# FPC-024.net
KiCad netlist of a schematic drawn in EasyEDA
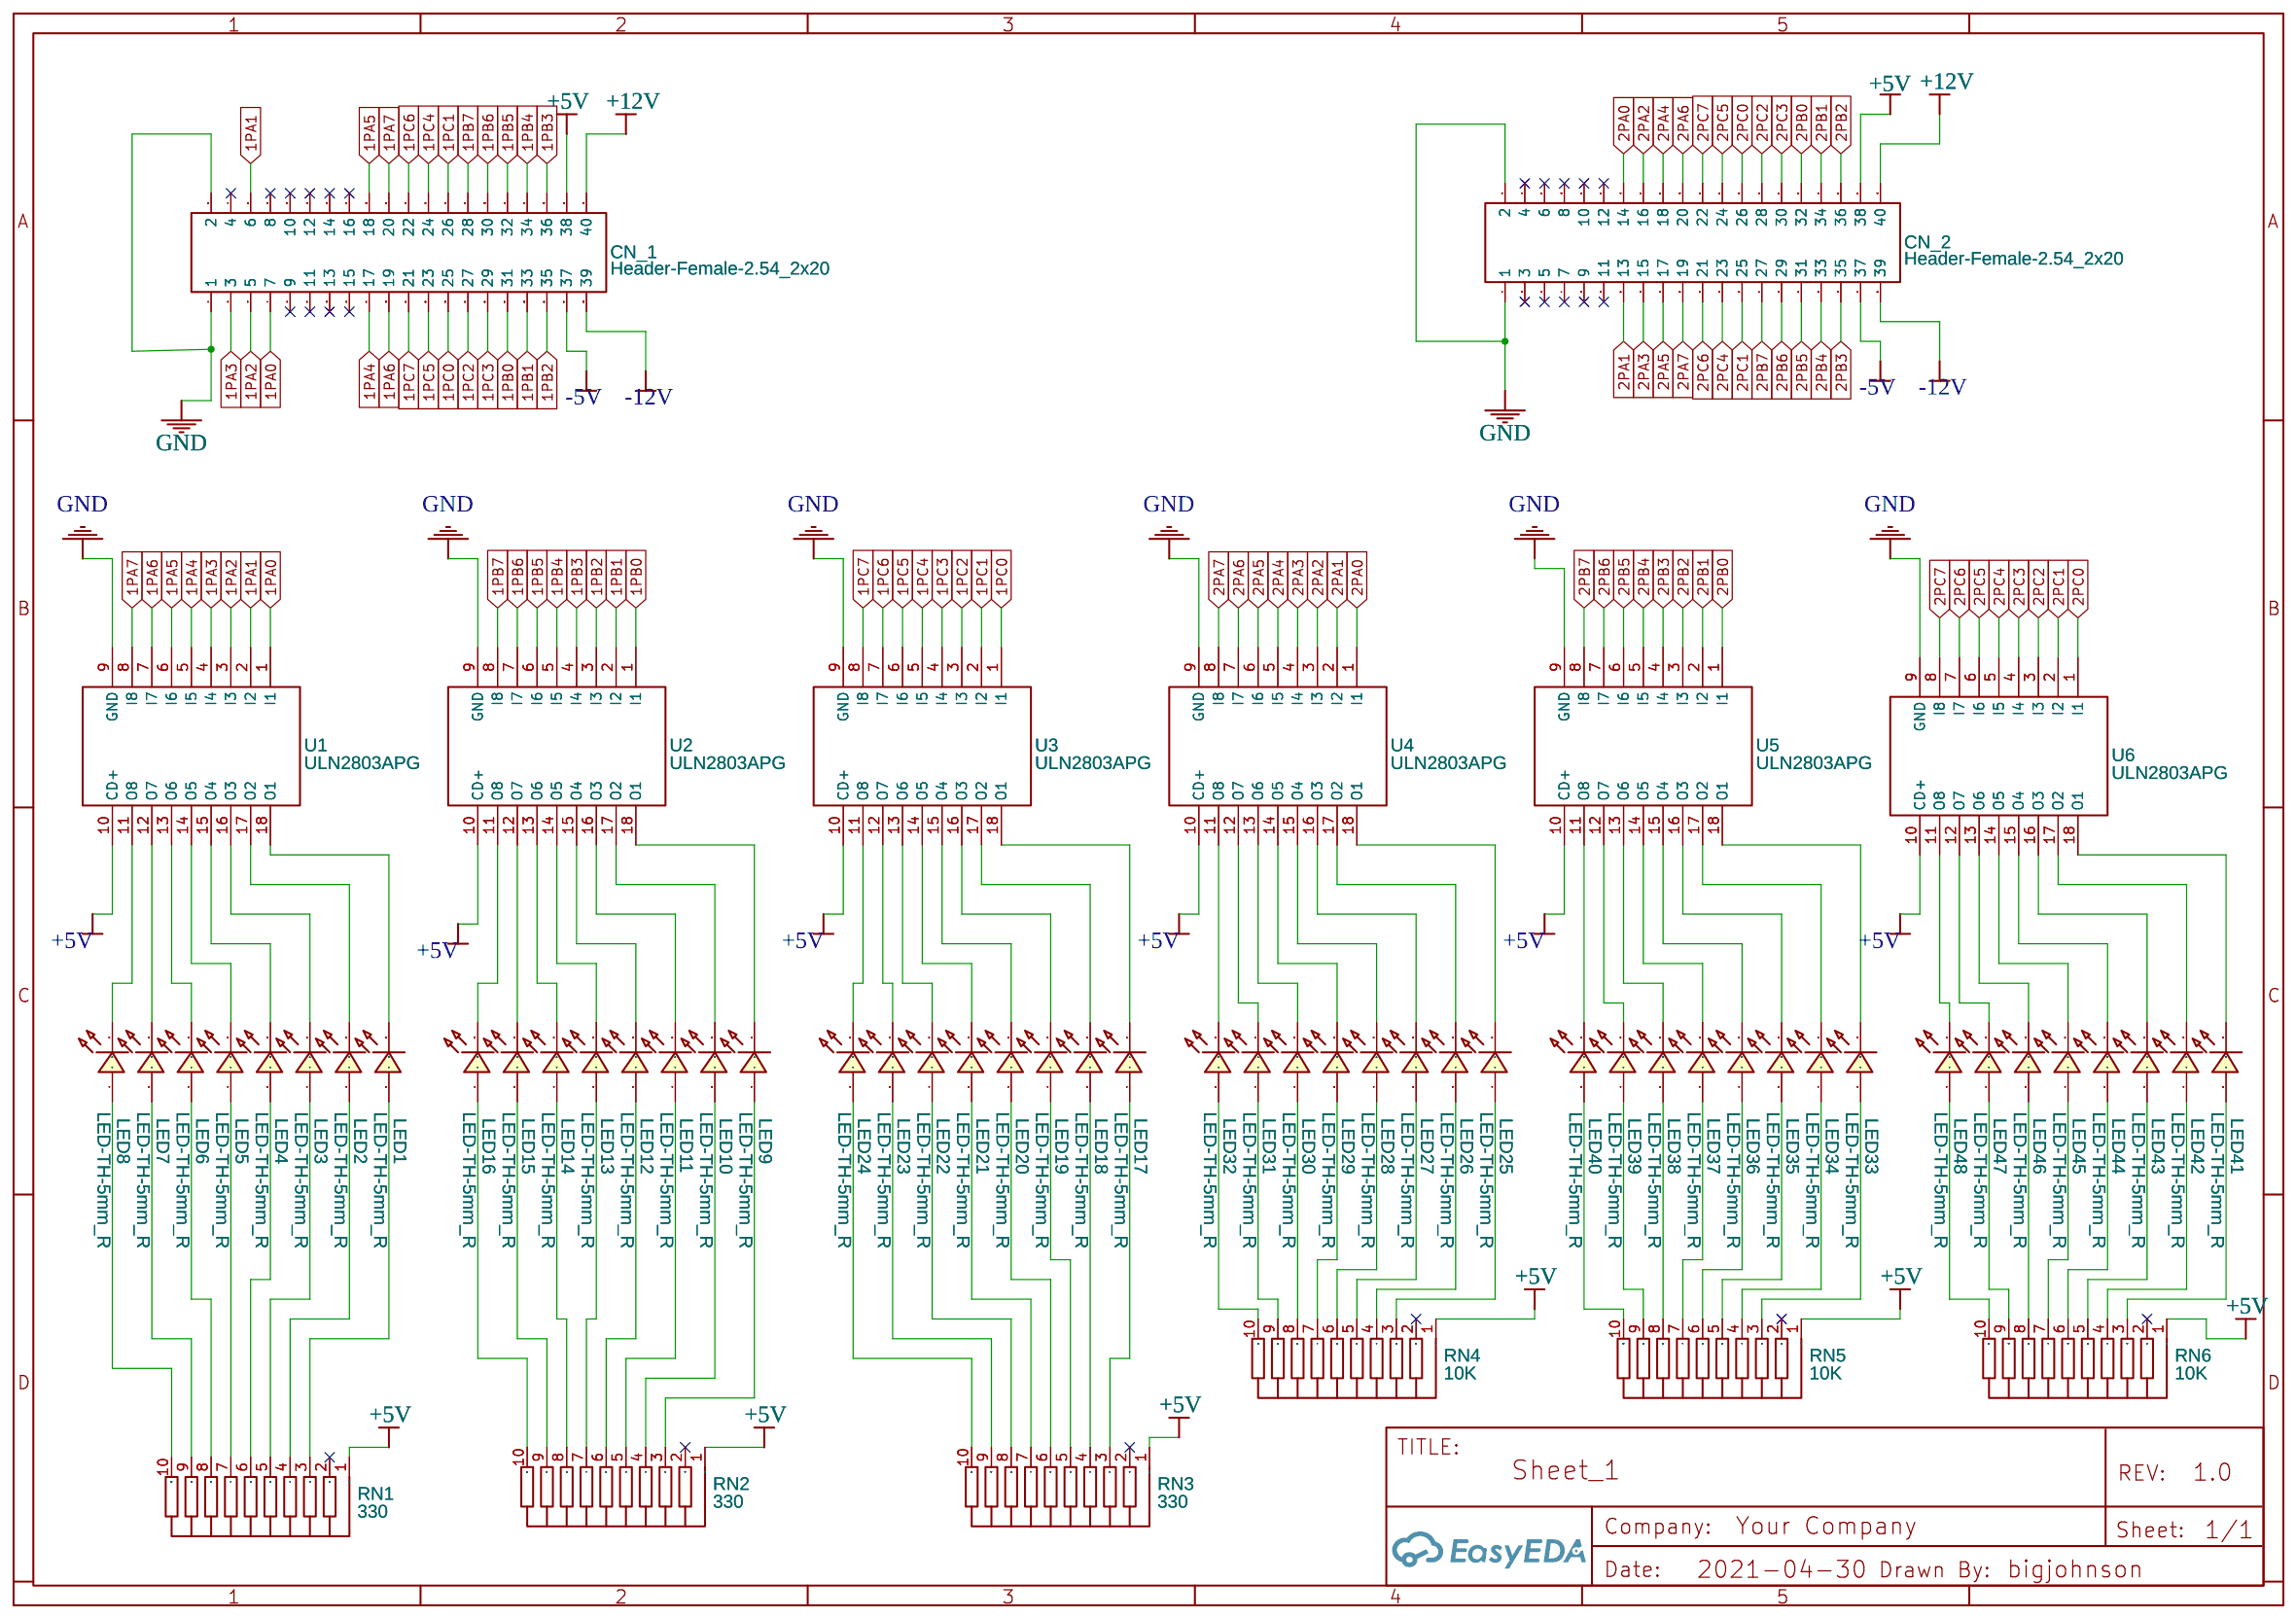
[diagram p0: schematic sheet]

(export (version "E")
  (design (tool "Eeschema 10.0.6"))
  (components
    (comp (ref "CN_1")
      (value "Header-Female-2.54_2x20")
      (fields
        (field (name "BOM_Manufacturer Part") "2.54mm 2*20PFemale header")
        (field (name "BOM_Supplier Part") "C50982")
      )
      (libsource (lib "") (part "Header-Female-2.54_2x20"))
    )
    (comp (ref "CN_2")
      (value "Header-Female-2.54_2x20")
      (fields
        (field (name "BOM_Manufacturer Part") "2.54mm 2*20PFemale header")
        (field (name "BOM_Supplier Part") "C50982")
      )
      (libsource (lib "") (part "Header-Female-2.54_2x20_1"))
    )
    (comp (ref "LED1")
      (value "LED-TH-5mm_R")
      (fields
        (field (name "BOM_Manufacturer Part") "333-2SURD/S530-A3")
        (field (name "BOM_Supplier Part") "C87271")
      )
      (libsource (lib "") (part "LED-TH-5mm_R"))
    )
    (comp (ref "LED2")
      (value "LED-TH-5mm_R")
      (fields
        (field (name "BOM_Manufacturer Part") "333-2SURD/S530-A3")
        (field (name "BOM_Supplier Part") "C87271")
      )
      (libsource (lib "") (part "LED-TH-5mm_R"))
    )
    (comp (ref "LED3")
      (value "LED-TH-5mm_R")
      (fields
        (field (name "BOM_Manufacturer Part") "333-2SURD/S530-A3")
        (field (name "BOM_Supplier Part") "C87271")
      )
      (libsource (lib "") (part "LED-TH-5mm_R"))
    )
    (comp (ref "LED4")
      (value "LED-TH-5mm_R")
      (fields
        (field (name "BOM_Manufacturer Part") "333-2SURD/S530-A3")
        (field (name "BOM_Supplier Part") "C87271")
      )
      (libsource (lib "") (part "LED-TH-5mm_R"))
    )
    (comp (ref "LED5")
      (value "LED-TH-5mm_R")
      (fields
        (field (name "BOM_Manufacturer Part") "333-2SURD/S530-A3")
        (field (name "BOM_Supplier Part") "C87271")
      )
      (libsource (lib "") (part "LED-TH-5mm_R"))
    )
    (comp (ref "LED6")
      (value "LED-TH-5mm_R")
      (fields
        (field (name "BOM_Manufacturer Part") "333-2SURD/S530-A3")
        (field (name "BOM_Supplier Part") "C87271")
      )
      (libsource (lib "") (part "LED-TH-5mm_R"))
    )
    (comp (ref "LED7")
      (value "LED-TH-5mm_R")
      (fields
        (field (name "BOM_Manufacturer Part") "333-2SURD/S530-A3")
        (field (name "BOM_Supplier Part") "C87271")
      )
      (libsource (lib "") (part "LED-TH-5mm_R"))
    )
    (comp (ref "LED8")
      (value "LED-TH-5mm_R")
      (fields
        (field (name "BOM_Manufacturer Part") "333-2SURD/S530-A3")
        (field (name "BOM_Supplier Part") "C87271")
      )
      (libsource (lib "") (part "LED-TH-5mm_R"))
    )
    (comp (ref "LED9")
      (value "LED-TH-5mm_R")
      (fields
        (field (name "BOM_Manufacturer Part") "333-2SURD/S530-A3")
        (field (name "BOM_Supplier Part") "C87271")
      )
      (libsource (lib "") (part "LED-TH-5mm_R"))
    )
    (comp (ref "LED10")
      (value "LED-TH-5mm_R")
      (fields
        (field (name "BOM_Manufacturer Part") "333-2SURD/S530-A3")
        (field (name "BOM_Supplier Part") "C87271")
      )
      (libsource (lib "") (part "LED-TH-5mm_R"))
    )
    (comp (ref "LED11")
      (value "LED-TH-5mm_R")
      (fields
        (field (name "BOM_Manufacturer Part") "333-2SURD/S530-A3")
        (field (name "BOM_Supplier Part") "C87271")
      )
      (libsource (lib "") (part "LED-TH-5mm_R"))
    )
    (comp (ref "LED12")
      (value "LED-TH-5mm_R")
      (fields
        (field (name "BOM_Manufacturer Part") "333-2SURD/S530-A3")
        (field (name "BOM_Supplier Part") "C87271")
      )
      (libsource (lib "") (part "LED-TH-5mm_R"))
    )
    (comp (ref "LED13")
      (value "LED-TH-5mm_R")
      (fields
        (field (name "BOM_Manufacturer Part") "333-2SURD/S530-A3")
        (field (name "BOM_Supplier Part") "C87271")
      )
      (libsource (lib "") (part "LED-TH-5mm_R"))
    )
    (comp (ref "LED14")
      (value "LED-TH-5mm_R")
      (fields
        (field (name "BOM_Manufacturer Part") "333-2SURD/S530-A3")
        (field (name "BOM_Supplier Part") "C87271")
      )
      (libsource (lib "") (part "LED-TH-5mm_R"))
    )
    (comp (ref "LED15")
      (value "LED-TH-5mm_R")
      (fields
        (field (name "BOM_Manufacturer Part") "333-2SURD/S530-A3")
        (field (name "BOM_Supplier Part") "C87271")
      )
      (libsource (lib "") (part "LED-TH-5mm_R"))
    )
    (comp (ref "LED16")
      (value "LED-TH-5mm_R")
      (fields
        (field (name "BOM_Manufacturer Part") "333-2SURD/S530-A3")
        (field (name "BOM_Supplier Part") "C87271")
      )
      (libsource (lib "") (part "LED-TH-5mm_R"))
    )
    (comp (ref "LED17")
      (value "LED-TH-5mm_R")
      (fields
        (field (name "BOM_Manufacturer Part") "333-2SURD/S530-A3")
        (field (name "BOM_Supplier Part") "C87271")
      )
      (libsource (lib "") (part "LED-TH-5mm_R"))
    )
    (comp (ref "LED18")
      (value "LED-TH-5mm_R")
      (fields
        (field (name "BOM_Manufacturer Part") "333-2SURD/S530-A3")
        (field (name "BOM_Supplier Part") "C87271")
      )
      (libsource (lib "") (part "LED-TH-5mm_R"))
    )
    (comp (ref "LED19")
      (value "LED-TH-5mm_R")
      (fields
        (field (name "BOM_Manufacturer Part") "333-2SURD/S530-A3")
        (field (name "BOM_Supplier Part") "C87271")
      )
      (libsource (lib "") (part "LED-TH-5mm_R"))
    )
    (comp (ref "LED20")
      (value "LED-TH-5mm_R")
      (fields
        (field (name "BOM_Manufacturer Part") "333-2SURD/S530-A3")
        (field (name "BOM_Supplier Part") "C87271")
      )
      (libsource (lib "") (part "LED-TH-5mm_R"))
    )
    (comp (ref "LED21")
      (value "LED-TH-5mm_R")
      (fields
        (field (name "BOM_Manufacturer Part") "333-2SURD/S530-A3")
        (field (name "BOM_Supplier Part") "C87271")
      )
      (libsource (lib "") (part "LED-TH-5mm_R"))
    )
    (comp (ref "LED22")
      (value "LED-TH-5mm_R")
      (fields
        (field (name "BOM_Manufacturer Part") "333-2SURD/S530-A3")
        (field (name "BOM_Supplier Part") "C87271")
      )
      (libsource (lib "") (part "LED-TH-5mm_R"))
    )
    (comp (ref "LED23")
      (value "LED-TH-5mm_R")
      (fields
        (field (name "BOM_Manufacturer Part") "333-2SURD/S530-A3")
        (field (name "BOM_Supplier Part") "C87271")
      )
      (libsource (lib "") (part "LED-TH-5mm_R"))
    )
    (comp (ref "LED24")
      (value "LED-TH-5mm_R")
      (fields
        (field (name "BOM_Manufacturer Part") "333-2SURD/S530-A3")
        (field (name "BOM_Supplier Part") "C87271")
      )
      (libsource (lib "") (part "LED-TH-5mm_R"))
    )
    (comp (ref "LED25")
      (value "LED-TH-5mm_R")
      (fields
        (field (name "BOM_Manufacturer Part") "333-2SURD/S530-A3")
        (field (name "BOM_Supplier Part") "C87271")
      )
      (libsource (lib "") (part "LED-TH-5mm_R"))
    )
    (comp (ref "LED26")
      (value "LED-TH-5mm_R")
      (fields
        (field (name "BOM_Manufacturer Part") "333-2SURD/S530-A3")
        (field (name "BOM_Supplier Part") "C87271")
      )
      (libsource (lib "") (part "LED-TH-5mm_R"))
    )
    (comp (ref "LED27")
      (value "LED-TH-5mm_R")
      (fields
        (field (name "BOM_Manufacturer Part") "333-2SURD/S530-A3")
        (field (name "BOM_Supplier Part") "C87271")
      )
      (libsource (lib "") (part "LED-TH-5mm_R"))
    )
    (comp (ref "LED28")
      (value "LED-TH-5mm_R")
      (fields
        (field (name "BOM_Manufacturer Part") "333-2SURD/S530-A3")
        (field (name "BOM_Supplier Part") "C87271")
      )
      (libsource (lib "") (part "LED-TH-5mm_R"))
    )
    (comp (ref "LED29")
      (value "LED-TH-5mm_R")
      (fields
        (field (name "BOM_Manufacturer Part") "333-2SURD/S530-A3")
        (field (name "BOM_Supplier Part") "C87271")
      )
      (libsource (lib "") (part "LED-TH-5mm_R"))
    )
    (comp (ref "LED30")
      (value "LED-TH-5mm_R")
      (fields
        (field (name "BOM_Manufacturer Part") "333-2SURD/S530-A3")
        (field (name "BOM_Supplier Part") "C87271")
      )
      (libsource (lib "") (part "LED-TH-5mm_R"))
    )
    (comp (ref "LED31")
      (value "LED-TH-5mm_R")
      (fields
        (field (name "BOM_Manufacturer Part") "333-2SURD/S530-A3")
        (field (name "BOM_Supplier Part") "C87271")
      )
      (libsource (lib "") (part "LED-TH-5mm_R"))
    )
    (comp (ref "LED32")
      (value "LED-TH-5mm_R")
      (fields
        (field (name "BOM_Manufacturer Part") "333-2SURD/S530-A3")
        (field (name "BOM_Supplier Part") "C87271")
      )
      (libsource (lib "") (part "LED-TH-5mm_R"))
    )
    (comp (ref "LED33")
      (value "LED-TH-5mm_R")
      (fields
        (field (name "BOM_Manufacturer Part") "333-2SURD/S530-A3")
        (field (name "BOM_Supplier Part") "C87271")
      )
      (libsource (lib "") (part "LED-TH-5mm_R"))
    )
    (comp (ref "LED34")
      (value "LED-TH-5mm_R")
      (fields
        (field (name "BOM_Manufacturer Part") "333-2SURD/S530-A3")
        (field (name "BOM_Supplier Part") "C87271")
      )
      (libsource (lib "") (part "LED-TH-5mm_R"))
    )
    (comp (ref "LED35")
      (value "LED-TH-5mm_R")
      (fields
        (field (name "BOM_Manufacturer Part") "333-2SURD/S530-A3")
        (field (name "BOM_Supplier Part") "C87271")
      )
      (libsource (lib "") (part "LED-TH-5mm_R"))
    )
    (comp (ref "LED36")
      (value "LED-TH-5mm_R")
      (fields
        (field (name "BOM_Manufacturer Part") "333-2SURD/S530-A3")
        (field (name "BOM_Supplier Part") "C87271")
      )
      (libsource (lib "") (part "LED-TH-5mm_R"))
    )
    (comp (ref "LED37")
      (value "LED-TH-5mm_R")
      (fields
        (field (name "BOM_Manufacturer Part") "333-2SURD/S530-A3")
        (field (name "BOM_Supplier Part") "C87271")
      )
      (libsource (lib "") (part "LED-TH-5mm_R"))
    )
    (comp (ref "LED38")
      (value "LED-TH-5mm_R")
      (fields
        (field (name "BOM_Manufacturer Part") "333-2SURD/S530-A3")
        (field (name "BOM_Supplier Part") "C87271")
      )
      (libsource (lib "") (part "LED-TH-5mm_R"))
    )
    (comp (ref "LED39")
      (value "LED-TH-5mm_R")
      (fields
        (field (name "BOM_Manufacturer Part") "333-2SURD/S530-A3")
        (field (name "BOM_Supplier Part") "C87271")
      )
      (libsource (lib "") (part "LED-TH-5mm_R"))
    )
    (comp (ref "LED40")
      (value "LED-TH-5mm_R")
      (fields
        (field (name "BOM_Manufacturer Part") "333-2SURD/S530-A3")
        (field (name "BOM_Supplier Part") "C87271")
      )
      (libsource (lib "") (part "LED-TH-5mm_R"))
    )
    (comp (ref "LED41")
      (value "LED-TH-5mm_R")
      (fields
        (field (name "BOM_Manufacturer Part") "333-2SURD/S530-A3")
        (field (name "BOM_Supplier Part") "C87271")
      )
      (libsource (lib "") (part "LED-TH-5mm_R"))
    )
    (comp (ref "LED42")
      (value "LED-TH-5mm_R")
      (fields
        (field (name "BOM_Manufacturer Part") "333-2SURD/S530-A3")
        (field (name "BOM_Supplier Part") "C87271")
      )
      (libsource (lib "") (part "LED-TH-5mm_R"))
    )
    (comp (ref "LED43")
      (value "LED-TH-5mm_R")
      (fields
        (field (name "BOM_Manufacturer Part") "333-2SURD/S530-A3")
        (field (name "BOM_Supplier Part") "C87271")
      )
      (libsource (lib "") (part "LED-TH-5mm_R"))
    )
    (comp (ref "LED44")
      (value "LED-TH-5mm_R")
      (fields
        (field (name "BOM_Manufacturer Part") "333-2SURD/S530-A3")
        (field (name "BOM_Supplier Part") "C87271")
      )
      (libsource (lib "") (part "LED-TH-5mm_R"))
    )
    (comp (ref "LED45")
      (value "LED-TH-5mm_R")
      (fields
        (field (name "BOM_Manufacturer Part") "333-2SURD/S530-A3")
        (field (name "BOM_Supplier Part") "C87271")
      )
      (libsource (lib "") (part "LED-TH-5mm_R"))
    )
    (comp (ref "LED46")
      (value "LED-TH-5mm_R")
      (fields
        (field (name "BOM_Manufacturer Part") "333-2SURD/S530-A3")
        (field (name "BOM_Supplier Part") "C87271")
      )
      (libsource (lib "") (part "LED-TH-5mm_R"))
    )
    (comp (ref "LED47")
      (value "LED-TH-5mm_R")
      (fields
        (field (name "BOM_Manufacturer Part") "333-2SURD/S530-A3")
        (field (name "BOM_Supplier Part") "C87271")
      )
      (libsource (lib "") (part "LED-TH-5mm_R"))
    )
    (comp (ref "LED48")
      (value "LED-TH-5mm_R")
      (fields
        (field (name "BOM_Manufacturer Part") "333-2SURD/S530-A3")
        (field (name "BOM_Supplier Part") "C87271")
      )
      (libsource (lib "") (part "LED-TH-5mm_R"))
    )
    (comp (ref "RN1")
      (value "330")
      (fields (field (name "BOM_Manufacturer Part") "RAA10103G") (field (name "BOM_Supplier Part") "C353599"))
      (libsource (lib "") (part "RAA10103G"))
    )
    (comp (ref "RN2")
      (value "330")
      (fields (field (name "BOM_Manufacturer Part") "RAA10103G") (field (name "BOM_Supplier Part") "C353599"))
      (libsource (lib "") (part "RAA10103G"))
    )
    (comp (ref "RN3")
      (value "330")
      (fields (field (name "BOM_Manufacturer Part") "RAA10103G") (field (name "BOM_Supplier Part") "C353599"))
      (libsource (lib "") (part "RAA10103G"))
    )
    (comp (ref "RN4")
      (value "10K")
      (fields (field (name "BOM_Manufacturer Part") "RAA10103G") (field (name "BOM_Supplier Part") "C353599"))
      (libsource (lib "") (part "RAA10103G"))
    )
    (comp (ref "RN5")
      (value "10K")
      (fields (field (name "BOM_Manufacturer Part") "RAA10103G") (field (name "BOM_Supplier Part") "C353599"))
      (libsource (lib "") (part "RAA10103G"))
    )
    (comp (ref "RN6")
      (value "10K")
      (fields (field (name "BOM_Manufacturer Part") "RAA10103G") (field (name "BOM_Supplier Part") "C353599"))
      (libsource (lib "") (part "RAA10103G"))
    )
    (comp (ref "U1")
      (value "ULN2803APG")
      (fields (field (name "BOM_Supplier Part") "C5252"))
      (libsource (lib "") (part "ULN2803APG"))
    )
    (comp (ref "U2")
      (value "ULN2803APG")
      (fields (field (name "BOM_Supplier Part") "C5252"))
      (libsource (lib "") (part "ULN2803APG"))
    )
    (comp (ref "U3")
      (value "ULN2803APG")
      (fields (field (name "BOM_Supplier Part") "C5252"))
      (libsource (lib "") (part "ULN2803APG"))
    )
    (comp (ref "U4")
      (value "ULN2803APG")
      (fields (field (name "BOM_Supplier Part") "C5252"))
      (libsource (lib "") (part "ULN2803APG"))
    )
    (comp (ref "U5")
      (value "ULN2803APG")
      (fields (field (name "BOM_Supplier Part") "C5252"))
      (libsource (lib "") (part "ULN2803APG"))
    )
    (comp (ref "U6")
      (value "ULN2803APG")
      (fields (field (name "BOM_Supplier Part") "C5252"))
      (libsource (lib "") (part "ULN2803APG"))
    )
  )
  (nets
    (net (code "1") (name "+5V") (class "Default")
      (node (ref "CN_1") (pin "38") (pinfunction "38_38") (pintype "input"))
      (node (ref "CN_2") (pin "38") (pinfunction "38_38") (pintype "input"))
      (node (ref "RN1") (pin "1") (pinfunction "1_1") (pintype "unspecified"))
      (node (ref "RN2") (pin "1") (pinfunction "1_1") (pintype "unspecified"))
      (node (ref "RN3") (pin "1") (pinfunction "1_1") (pintype "unspecified"))
      (node (ref "RN4") (pin "1") (pinfunction "1_1") (pintype "unspecified"))
      (node (ref "RN5") (pin "1") (pinfunction "1_1") (pintype "unspecified"))
      (node (ref "RN6") (pin "1") (pinfunction "1_1") (pintype "unspecified"))
      (node (ref "U1") (pin "10") (pinfunction "CD+_10") (pintype "unspecified"))
      (node (ref "U2") (pin "10") (pinfunction "CD+_10") (pintype "unspecified"))
      (node (ref "U3") (pin "10") (pinfunction "CD+_10") (pintype "unspecified"))
      (node (ref "U4") (pin "10") (pinfunction "CD+_10") (pintype "unspecified"))
      (node (ref "U5") (pin "10") (pinfunction "CD+_10") (pintype "unspecified"))
      (node (ref "U6") (pin "10") (pinfunction "CD+_10") (pintype "unspecified"))
    )
    (net (code "2") (name "+12V") (class "Default")
      (node (ref "CN_1") (pin "40") (pinfunction "40_40") (pintype "input"))
      (node (ref "CN_2") (pin "40") (pinfunction "40_40") (pintype "input"))
    )
    (net (code "3") (name "-5V") (class "Default")
      (node (ref "CN_1") (pin "37") (pinfunction "37_37") (pintype "input"))
      (node (ref "CN_2") (pin "37") (pinfunction "37_37") (pintype "input"))
    )
    (net (code "4") (name "-12V") (class "Default")
      (node (ref "CN_1") (pin "39") (pinfunction "39_39") (pintype "input"))
      (node (ref "CN_2") (pin "39") (pinfunction "39_39") (pintype "input"))
    )
    (net (code "5") (name "1PA0") (class "Default")
      (node (ref "CN_1") (pin "7") (pinfunction "7_7") (pintype "input"))
      (node (ref "U1") (pin "1") (pinfunction "I1_1") (pintype "input"))
    )
    (net (code "6") (name "1PA1") (class "Default")
      (node (ref "CN_1") (pin "6") (pinfunction "6_6") (pintype "input"))
      (node (ref "U1") (pin "2") (pinfunction "I2_2") (pintype "input"))
    )
    (net (code "7") (name "1PA2") (class "Default")
      (node (ref "CN_1") (pin "5") (pinfunction "5_5") (pintype "input"))
      (node (ref "U1") (pin "3") (pinfunction "I3_3") (pintype "input"))
    )
    (net (code "8") (name "1PA3") (class "Default")
      (node (ref "CN_1") (pin "3") (pinfunction "3_3") (pintype "input"))
      (node (ref "U1") (pin "4") (pinfunction "I4_4") (pintype "input"))
    )
    (net (code "9") (name "1PA4") (class "Default")
      (node (ref "CN_1") (pin "17") (pinfunction "17_17") (pintype "input"))
      (node (ref "U1") (pin "5") (pinfunction "I5_5") (pintype "input"))
    )
    (net (code "10") (name "1PA5") (class "Default")
      (node (ref "CN_1") (pin "18") (pinfunction "18_18") (pintype "input"))
      (node (ref "U1") (pin "6") (pinfunction "I6_6") (pintype "input"))
    )
    (net (code "11") (name "1PA6") (class "Default")
      (node (ref "CN_1") (pin "19") (pinfunction "19_19") (pintype "input"))
      (node (ref "U1") (pin "7") (pinfunction "I7_7") (pintype "input"))
    )
    (net (code "12") (name "1PA7") (class "Default")
      (node (ref "CN_1") (pin "20") (pinfunction "20_20") (pintype "input"))
      (node (ref "U1") (pin "8") (pinfunction "I8_8") (pintype "input"))
    )
    (net (code "13") (name "1PB0") (class "Default")
      (node (ref "CN_1") (pin "31") (pinfunction "31_31") (pintype "input"))
      (node (ref "U2") (pin "1") (pinfunction "I1_1") (pintype "input"))
    )
    (net (code "14") (name "1PB1") (class "Default")
      (node (ref "CN_1") (pin "33") (pinfunction "33_33") (pintype "input"))
      (node (ref "U2") (pin "2") (pinfunction "I2_2") (pintype "input"))
    )
    (net (code "15") (name "1PB2") (class "Default")
      (node (ref "CN_1") (pin "35") (pinfunction "35_35") (pintype "input"))
      (node (ref "U2") (pin "3") (pinfunction "I3_3") (pintype "input"))
    )
    (net (code "16") (name "1PB3") (class "Default")
      (node (ref "CN_1") (pin "36") (pinfunction "36_36") (pintype "input"))
      (node (ref "U2") (pin "4") (pinfunction "I4_4") (pintype "input"))
    )
    (net (code "17") (name "1PB4") (class "Default")
      (node (ref "CN_1") (pin "34") (pinfunction "34_34") (pintype "input"))
      (node (ref "U2") (pin "5") (pinfunction "I5_5") (pintype "input"))
    )
    (net (code "18") (name "1PB5") (class "Default")
      (node (ref "CN_1") (pin "32") (pinfunction "32_32") (pintype "input"))
      (node (ref "U2") (pin "6") (pinfunction "I6_6") (pintype "input"))
    )
    (net (code "19") (name "1PB6") (class "Default")
      (node (ref "CN_1") (pin "30") (pinfunction "30_30") (pintype "input"))
      (node (ref "U2") (pin "7") (pinfunction "I7_7") (pintype "input"))
    )
    (net (code "20") (name "1PB7") (class "Default")
      (node (ref "CN_1") (pin "28") (pinfunction "28_28") (pintype "input"))
      (node (ref "U2") (pin "8") (pinfunction "I8_8") (pintype "input"))
    )
    (net (code "21") (name "1PC0") (class "Default")
      (node (ref "CN_1") (pin "25") (pinfunction "25_25") (pintype "input"))
      (node (ref "U3") (pin "1") (pinfunction "I1_1") (pintype "input"))
    )
    (net (code "22") (name "1PC1") (class "Default")
      (node (ref "CN_1") (pin "26") (pinfunction "26_26") (pintype "input"))
      (node (ref "U3") (pin "2") (pinfunction "I2_2") (pintype "input"))
    )
    (net (code "23") (name "1PC2") (class "Default")
      (node (ref "CN_1") (pin "27") (pinfunction "27_27") (pintype "input"))
      (node (ref "U3") (pin "3") (pinfunction "I3_3") (pintype "input"))
    )
    (net (code "24") (name "1PC3") (class "Default")
      (node (ref "CN_1") (pin "29") (pinfunction "29_29") (pintype "input"))
      (node (ref "U3") (pin "4") (pinfunction "I4_4") (pintype "input"))
    )
    (net (code "25") (name "1PC4") (class "Default")
      (node (ref "CN_1") (pin "24") (pinfunction "24_24") (pintype "input"))
      (node (ref "U3") (pin "5") (pinfunction "I5_5") (pintype "input"))
    )
    (net (code "26") (name "1PC5") (class "Default")
      (node (ref "CN_1") (pin "23") (pinfunction "23_23") (pintype "input"))
      (node (ref "U3") (pin "6") (pinfunction "I6_6") (pintype "input"))
    )
    (net (code "27") (name "1PC6") (class "Default")
      (node (ref "CN_1") (pin "22") (pinfunction "22_22") (pintype "input"))
      (node (ref "U3") (pin "7") (pinfunction "I7_7") (pintype "input"))
    )
    (net (code "28") (name "1PC7") (class "Default")
      (node (ref "CN_1") (pin "21") (pinfunction "21_21") (pintype "input"))
      (node (ref "U3") (pin "8") (pinfunction "I8_8") (pintype "input"))
    )
    (net (code "29") (name "2PA0") (class "Default")
      (node (ref "CN_2") (pin "14") (pinfunction "14_14") (pintype "input"))
      (node (ref "U4") (pin "1") (pinfunction "I1_1") (pintype "input"))
    )
    (net (code "30") (name "2PA1") (class "Default")
      (node (ref "CN_2") (pin "13") (pinfunction "13_13") (pintype "input"))
      (node (ref "U4") (pin "2") (pinfunction "I2_2") (pintype "input"))
    )
    (net (code "31") (name "2PA2") (class "Default")
      (node (ref "CN_2") (pin "16") (pinfunction "16_16") (pintype "input"))
      (node (ref "U4") (pin "3") (pinfunction "I3_3") (pintype "input"))
    )
    (net (code "32") (name "2PA3") (class "Default")
      (node (ref "CN_2") (pin "15") (pinfunction "15_15") (pintype "input"))
      (node (ref "U4") (pin "4") (pinfunction "I4_4") (pintype "input"))
    )
    (net (code "33") (name "2PA4") (class "Default")
      (node (ref "CN_2") (pin "18") (pinfunction "18_18") (pintype "input"))
      (node (ref "U4") (pin "5") (pinfunction "I5_5") (pintype "input"))
    )
    (net (code "34") (name "2PA5") (class "Default")
      (node (ref "CN_2") (pin "17") (pinfunction "17_17") (pintype "input"))
      (node (ref "U4") (pin "6") (pinfunction "I6_6") (pintype "input"))
    )
    (net (code "35") (name "2PA6") (class "Default")
      (node (ref "CN_2") (pin "20") (pinfunction "20_20") (pintype "input"))
      (node (ref "U4") (pin "7") (pinfunction "I7_7") (pintype "input"))
    )
    (net (code "36") (name "2PA7") (class "Default")
      (node (ref "CN_2") (pin "19") (pinfunction "19_19") (pintype "input"))
      (node (ref "U4") (pin "8") (pinfunction "I8_8") (pintype "input"))
    )
    (net (code "37") (name "2PB0") (class "Default")
      (node (ref "CN_2") (pin "32") (pinfunction "32_32") (pintype "input"))
      (node (ref "U5") (pin "1") (pinfunction "I1_1") (pintype "input"))
    )
    (net (code "38") (name "2PB1") (class "Default")
      (node (ref "CN_2") (pin "34") (pinfunction "34_34") (pintype "input"))
      (node (ref "U5") (pin "2") (pinfunction "I2_2") (pintype "input"))
    )
    (net (code "39") (name "2PB2") (class "Default")
      (node (ref "CN_2") (pin "36") (pinfunction "36_36") (pintype "input"))
      (node (ref "U5") (pin "3") (pinfunction "I3_3") (pintype "input"))
    )
    (net (code "40") (name "2PB3") (class "Default")
      (node (ref "CN_2") (pin "35") (pinfunction "35_35") (pintype "input"))
      (node (ref "U5") (pin "4") (pinfunction "I4_4") (pintype "input"))
    )
    (net (code "41") (name "2PB4") (class "Default")
      (node (ref "CN_2") (pin "33") (pinfunction "33_33") (pintype "input"))
      (node (ref "U5") (pin "5") (pinfunction "I5_5") (pintype "input"))
    )
    (net (code "42") (name "2PB5") (class "Default")
      (node (ref "CN_2") (pin "31") (pinfunction "31_31") (pintype "input"))
      (node (ref "U5") (pin "6") (pinfunction "I6_6") (pintype "input"))
    )
    (net (code "43") (name "2PB6") (class "Default")
      (node (ref "CN_2") (pin "29") (pinfunction "29_29") (pintype "input"))
      (node (ref "U5") (pin "7") (pinfunction "I7_7") (pintype "input"))
    )
    (net (code "44") (name "2PB7") (class "Default")
      (node (ref "CN_2") (pin "27") (pinfunction "27_27") (pintype "input"))
      (node (ref "U5") (pin "8") (pinfunction "I8_8") (pintype "input"))
    )
    (net (code "45") (name "2PC0") (class "Default")
      (node (ref "CN_2") (pin "26") (pinfunction "26_26") (pintype "input"))
      (node (ref "U6") (pin "1") (pinfunction "I1_1") (pintype "input"))
    )
    (net (code "46") (name "2PC1") (class "Default")
      (node (ref "CN_2") (pin "25") (pinfunction "25_25") (pintype "input"))
      (node (ref "U6") (pin "2") (pinfunction "I2_2") (pintype "input"))
    )
    (net (code "47") (name "2PC2") (class "Default")
      (node (ref "CN_2") (pin "28") (pinfunction "28_28") (pintype "input"))
      (node (ref "U6") (pin "3") (pinfunction "I3_3") (pintype "input"))
    )
    (net (code "48") (name "2PC3") (class "Default")
      (node (ref "CN_2") (pin "30") (pinfunction "30_30") (pintype "input"))
      (node (ref "U6") (pin "4") (pinfunction "I4_4") (pintype "input"))
    )
    (net (code "49") (name "2PC4") (class "Default")
      (node (ref "CN_2") (pin "23") (pinfunction "23_23") (pintype "input"))
      (node (ref "U6") (pin "5") (pinfunction "I5_5") (pintype "input"))
    )
    (net (code "50") (name "2PC5") (class "Default")
      (node (ref "CN_2") (pin "24") (pinfunction "24_24") (pintype "input"))
      (node (ref "U6") (pin "6") (pinfunction "I6_6") (pintype "input"))
    )
    (net (code "51") (name "2PC6") (class "Default")
      (node (ref "CN_2") (pin "21") (pinfunction "21_21") (pintype "input"))
      (node (ref "U6") (pin "7") (pinfunction "I7_7") (pintype "input"))
    )
    (net (code "52") (name "2PC7") (class "Default")
      (node (ref "CN_2") (pin "22") (pinfunction "22_22") (pintype "input"))
      (node (ref "U6") (pin "8") (pinfunction "I8_8") (pintype "input"))
    )
    (net (code "53") (name "GND") (class "Default")
      (node (ref "CN_1") (pin "1") (pinfunction "1_1") (pintype "passive"))
      (node (ref "CN_1") (pin "2") (pinfunction "2_2") (pintype "passive"))
      (node (ref "CN_2") (pin "1") (pinfunction "1_1") (pintype "input"))
      (node (ref "CN_2") (pin "2") (pinfunction "2_2") (pintype "input"))
      (node (ref "U1") (pin "9") (pinfunction "GND_9") (pintype "passive"))
      (node (ref "U2") (pin "9") (pinfunction "GND_9") (pintype "passive"))
      (node (ref "U3") (pin "9") (pinfunction "GND_9") (pintype "passive"))
      (node (ref "U4") (pin "9") (pinfunction "GND_9") (pintype "passive"))
      (node (ref "U5") (pin "9") (pinfunction "GND_9") (pintype "passive"))
      (node (ref "U6") (pin "9") (pinfunction "GND_9") (pintype "passive"))
    )
    (net (code "54") (name "Net-(LED1-Pad1)") (class "Default")
      (node (ref "LED1") (pin "1") (pinfunction "1_1") (pintype "unspecified"))
      (node (ref "RN1") (pin "3") (pinfunction "3_3") (pintype "unspecified"))
    )
    (net (code "55") (name "Net-(LED2-Pad1)") (class "Default")
      (node (ref "LED2") (pin "1") (pinfunction "1_1") (pintype "unspecified"))
      (node (ref "RN1") (pin "4") (pinfunction "4_4") (pintype "unspecified"))
    )
    (net (code "56") (name "Net-(LED3-Pad1)") (class "Default")
      (node (ref "LED3") (pin "1") (pinfunction "1_1") (pintype "unspecified"))
      (node (ref "RN1") (pin "5") (pinfunction "5_5") (pintype "unspecified"))
    )
    (net (code "57") (name "Net-(LED4-Pad1)") (class "Default")
      (node (ref "LED4") (pin "1") (pinfunction "1_1") (pintype "unspecified"))
      (node (ref "RN1") (pin "6") (pinfunction "6_6") (pintype "unspecified"))
    )
    (net (code "58") (name "Net-(LED5-Pad1)") (class "Default")
      (node (ref "LED5") (pin "1") (pinfunction "1_1") (pintype "unspecified"))
      (node (ref "RN1") (pin "7") (pinfunction "7_7") (pintype "unspecified"))
    )
    (net (code "59") (name "Net-(LED6-Pad1)") (class "Default")
      (node (ref "LED6") (pin "1") (pinfunction "1_1") (pintype "unspecified"))
      (node (ref "RN1") (pin "8") (pinfunction "8_8") (pintype "unspecified"))
    )
    (net (code "60") (name "Net-(LED7-Pad1)") (class "Default")
      (node (ref "LED7") (pin "1") (pinfunction "1_1") (pintype "unspecified"))
      (node (ref "RN1") (pin "9") (pinfunction "9_9") (pintype "unspecified"))
    )
    (net (code "61") (name "Net-(LED8-Pad1)") (class "Default")
      (node (ref "LED8") (pin "1") (pinfunction "1_1") (pintype "unspecified"))
      (node (ref "RN1") (pin "10") (pinfunction "10_10") (pintype "unspecified"))
    )
    (net (code "62") (name "Net-(LED9-Pad1)") (class "Default")
      (node (ref "LED9") (pin "1") (pinfunction "1_1") (pintype "unspecified"))
      (node (ref "RN2") (pin "3") (pinfunction "3_3") (pintype "unspecified"))
    )
    (net (code "63") (name "Net-(LED10-Pad1)") (class "Default")
      (node (ref "LED10") (pin "1") (pinfunction "1_1") (pintype "unspecified"))
      (node (ref "RN2") (pin "4") (pinfunction "4_4") (pintype "unspecified"))
    )
    (net (code "64") (name "Net-(LED11-Pad1)") (class "Default")
      (node (ref "LED11") (pin "1") (pinfunction "1_1") (pintype "unspecified"))
      (node (ref "RN2") (pin "5") (pinfunction "5_5") (pintype "unspecified"))
    )
    (net (code "65") (name "Net-(LED12-Pad1)") (class "Default")
      (node (ref "LED12") (pin "1") (pinfunction "1_1") (pintype "unspecified"))
      (node (ref "RN2") (pin "6") (pinfunction "6_6") (pintype "unspecified"))
    )
    (net (code "66") (name "Net-(LED13-Pad1)") (class "Default")
      (node (ref "LED13") (pin "1") (pinfunction "1_1") (pintype "unspecified"))
      (node (ref "RN2") (pin "7") (pinfunction "7_7") (pintype "unspecified"))
    )
    (net (code "67") (name "Net-(LED14-Pad1)") (class "Default")
      (node (ref "LED14") (pin "1") (pinfunction "1_1") (pintype "unspecified"))
      (node (ref "RN2") (pin "8") (pinfunction "8_8") (pintype "unspecified"))
    )
    (net (code "68") (name "Net-(LED15-Pad1)") (class "Default")
      (node (ref "LED15") (pin "1") (pinfunction "1_1") (pintype "unspecified"))
      (node (ref "RN2") (pin "9") (pinfunction "9_9") (pintype "unspecified"))
    )
    (net (code "69") (name "Net-(LED16-Pad1)") (class "Default")
      (node (ref "LED16") (pin "1") (pinfunction "1_1") (pintype "unspecified"))
      (node (ref "RN2") (pin "10") (pinfunction "10_10") (pintype "unspecified"))
    )
    (net (code "70") (name "Net-(LED17-Pad1)") (class "Default")
      (node (ref "LED17") (pin "1") (pinfunction "1_1") (pintype "unspecified"))
      (node (ref "RN3") (pin "3") (pinfunction "3_3") (pintype "unspecified"))
    )
    (net (code "71") (name "Net-(LED18-Pad1)") (class "Default")
      (node (ref "LED18") (pin "1") (pinfunction "1_1") (pintype "unspecified"))
      (node (ref "RN3") (pin "4") (pinfunction "4_4") (pintype "unspecified"))
    )
    (net (code "72") (name "Net-(LED19-Pad1)") (class "Default")
      (node (ref "LED19") (pin "1") (pinfunction "1_1") (pintype "unspecified"))
      (node (ref "RN3") (pin "5") (pinfunction "5_5") (pintype "unspecified"))
    )
    (net (code "73") (name "Net-(LED20-Pad1)") (class "Default")
      (node (ref "LED20") (pin "1") (pinfunction "1_1") (pintype "unspecified"))
      (node (ref "RN3") (pin "6") (pinfunction "6_6") (pintype "unspecified"))
    )
    (net (code "74") (name "Net-(LED21-Pad1)") (class "Default")
      (node (ref "LED21") (pin "1") (pinfunction "1_1") (pintype "unspecified"))
      (node (ref "RN3") (pin "7") (pinfunction "7_7") (pintype "unspecified"))
    )
    (net (code "75") (name "Net-(LED22-Pad1)") (class "Default")
      (node (ref "LED22") (pin "1") (pinfunction "1_1") (pintype "unspecified"))
      (node (ref "RN3") (pin "8") (pinfunction "8_8") (pintype "unspecified"))
    )
    (net (code "76") (name "Net-(LED23-Pad1)") (class "Default")
      (node (ref "LED23") (pin "1") (pinfunction "1_1") (pintype "unspecified"))
      (node (ref "RN3") (pin "9") (pinfunction "9_9") (pintype "unspecified"))
    )
    (net (code "77") (name "Net-(LED24-Pad1)") (class "Default")
      (node (ref "LED24") (pin "1") (pinfunction "1_1") (pintype "unspecified"))
      (node (ref "RN3") (pin "10") (pinfunction "10_10") (pintype "unspecified"))
    )
    (net (code "78") (name "Net-(LED25-Pad1)") (class "Default")
      (node (ref "LED25") (pin "1") (pinfunction "1_1") (pintype "unspecified"))
      (node (ref "RN4") (pin "3") (pinfunction "3_3") (pintype "unspecified"))
    )
    (net (code "79") (name "Net-(LED26-Pad1)") (class "Default")
      (node (ref "LED26") (pin "1") (pinfunction "1_1") (pintype "unspecified"))
      (node (ref "RN4") (pin "4") (pinfunction "4_4") (pintype "unspecified"))
    )
    (net (code "80") (name "Net-(LED27-Pad1)") (class "Default")
      (node (ref "LED27") (pin "1") (pinfunction "1_1") (pintype "unspecified"))
      (node (ref "RN4") (pin "5") (pinfunction "5_5") (pintype "unspecified"))
    )
    (net (code "81") (name "Net-(LED28-Pad1)") (class "Default")
      (node (ref "LED28") (pin "1") (pinfunction "1_1") (pintype "unspecified"))
      (node (ref "RN4") (pin "6") (pinfunction "6_6") (pintype "unspecified"))
    )
    (net (code "82") (name "Net-(LED29-Pad1)") (class "Default")
      (node (ref "LED29") (pin "1") (pinfunction "1_1") (pintype "unspecified"))
      (node (ref "RN4") (pin "7") (pinfunction "7_7") (pintype "unspecified"))
    )
    (net (code "83") (name "Net-(LED30-Pad1)") (class "Default")
      (node (ref "LED30") (pin "1") (pinfunction "1_1") (pintype "unspecified"))
      (node (ref "RN4") (pin "8") (pinfunction "8_8") (pintype "unspecified"))
    )
    (net (code "84") (name "Net-(LED31-Pad1)") (class "Default")
      (node (ref "LED31") (pin "1") (pinfunction "1_1") (pintype "unspecified"))
      (node (ref "RN4") (pin "9") (pinfunction "9_9") (pintype "unspecified"))
    )
    (net (code "85") (name "Net-(LED32-Pad1)") (class "Default")
      (node (ref "LED32") (pin "1") (pinfunction "1_1") (pintype "unspecified"))
      (node (ref "RN4") (pin "10") (pinfunction "10_10") (pintype "unspecified"))
    )
    (net (code "86") (name "Net-(LED33-Pad1)") (class "Default")
      (node (ref "LED33") (pin "1") (pinfunction "1_1") (pintype "unspecified"))
      (node (ref "RN5") (pin "3") (pinfunction "3_3") (pintype "unspecified"))
    )
    (net (code "87") (name "Net-(LED34-Pad1)") (class "Default")
      (node (ref "LED34") (pin "1") (pinfunction "1_1") (pintype "unspecified"))
      (node (ref "RN5") (pin "4") (pinfunction "4_4") (pintype "unspecified"))
    )
    (net (code "88") (name "Net-(LED35-Pad1)") (class "Default")
      (node (ref "LED35") (pin "1") (pinfunction "1_1") (pintype "unspecified"))
      (node (ref "RN5") (pin "5") (pinfunction "5_5") (pintype "unspecified"))
    )
    (net (code "89") (name "Net-(LED36-Pad1)") (class "Default")
      (node (ref "LED36") (pin "1") (pinfunction "1_1") (pintype "unspecified"))
      (node (ref "RN5") (pin "6") (pinfunction "6_6") (pintype "unspecified"))
    )
    (net (code "90") (name "Net-(LED37-Pad1)") (class "Default")
      (node (ref "LED37") (pin "1") (pinfunction "1_1") (pintype "unspecified"))
      (node (ref "RN5") (pin "7") (pinfunction "7_7") (pintype "unspecified"))
    )
    (net (code "91") (name "Net-(LED38-Pad1)") (class "Default")
      (node (ref "LED38") (pin "1") (pinfunction "1_1") (pintype "unspecified"))
      (node (ref "RN5") (pin "8") (pinfunction "8_8") (pintype "unspecified"))
    )
    (net (code "92") (name "Net-(LED39-Pad1)") (class "Default")
      (node (ref "LED39") (pin "1") (pinfunction "1_1") (pintype "unspecified"))
      (node (ref "RN5") (pin "9") (pinfunction "9_9") (pintype "unspecified"))
    )
    (net (code "93") (name "Net-(LED40-Pad1)") (class "Default")
      (node (ref "LED40") (pin "1") (pinfunction "1_1") (pintype "unspecified"))
      (node (ref "RN5") (pin "10") (pinfunction "10_10") (pintype "unspecified"))
    )
    (net (code "94") (name "Net-(LED41-Pad1)") (class "Default")
      (node (ref "LED41") (pin "1") (pinfunction "1_1") (pintype "unspecified"))
      (node (ref "RN6") (pin "3") (pinfunction "3_3") (pintype "unspecified"))
    )
    (net (code "95") (name "Net-(LED42-Pad1)") (class "Default")
      (node (ref "LED42") (pin "1") (pinfunction "1_1") (pintype "unspecified"))
      (node (ref "RN6") (pin "4") (pinfunction "4_4") (pintype "unspecified"))
    )
    (net (code "96") (name "Net-(LED43-Pad1)") (class "Default")
      (node (ref "LED43") (pin "1") (pinfunction "1_1") (pintype "unspecified"))
      (node (ref "RN6") (pin "5") (pinfunction "5_5") (pintype "unspecified"))
    )
    (net (code "97") (name "Net-(LED44-Pad1)") (class "Default")
      (node (ref "LED44") (pin "1") (pinfunction "1_1") (pintype "unspecified"))
      (node (ref "RN6") (pin "6") (pinfunction "6_6") (pintype "unspecified"))
    )
    (net (code "98") (name "Net-(LED45-Pad1)") (class "Default")
      (node (ref "LED45") (pin "1") (pinfunction "1_1") (pintype "unspecified"))
      (node (ref "RN6") (pin "7") (pinfunction "7_7") (pintype "unspecified"))
    )
    (net (code "99") (name "Net-(LED46-Pad1)") (class "Default")
      (node (ref "LED46") (pin "1") (pinfunction "1_1") (pintype "unspecified"))
      (node (ref "RN6") (pin "8") (pinfunction "8_8") (pintype "unspecified"))
    )
    (net (code "100") (name "Net-(LED47-Pad1)") (class "Default")
      (node (ref "LED47") (pin "1") (pinfunction "1_1") (pintype "unspecified"))
      (node (ref "RN6") (pin "9") (pinfunction "9_9") (pintype "unspecified"))
    )
    (net (code "101") (name "Net-(LED48-Pad1)") (class "Default")
      (node (ref "LED48") (pin "1") (pinfunction "1_1") (pintype "unspecified"))
      (node (ref "RN6") (pin "10") (pinfunction "10_10") (pintype "unspecified"))
    )
    (net (code "102") (name "Net-(U1-O1)") (class "Default")
      (node (ref "LED1") (pin "2") (pinfunction "2_2") (pintype "unspecified"))
      (node (ref "U1") (pin "18") (pinfunction "O1_18") (pintype "unspecified"))
    )
    (net (code "103") (name "Net-(U1-O2)") (class "Default")
      (node (ref "LED2") (pin "2") (pinfunction "2_2") (pintype "unspecified"))
      (node (ref "U1") (pin "17") (pinfunction "O2_17") (pintype "unspecified"))
    )
    (net (code "104") (name "Net-(U1-O3)") (class "Default")
      (node (ref "LED3") (pin "2") (pinfunction "2_2") (pintype "unspecified"))
      (node (ref "U1") (pin "16") (pinfunction "O3_16") (pintype "unspecified"))
    )
    (net (code "105") (name "Net-(U1-O4)") (class "Default")
      (node (ref "LED4") (pin "2") (pinfunction "2_2") (pintype "unspecified"))
      (node (ref "U1") (pin "15") (pinfunction "O4_15") (pintype "unspecified"))
    )
    (net (code "106") (name "Net-(U1-O5)") (class "Default")
      (node (ref "LED5") (pin "2") (pinfunction "2_2") (pintype "unspecified"))
      (node (ref "U1") (pin "14") (pinfunction "O5_14") (pintype "unspecified"))
    )
    (net (code "107") (name "Net-(U1-O6)") (class "Default")
      (node (ref "LED6") (pin "2") (pinfunction "2_2") (pintype "unspecified"))
      (node (ref "U1") (pin "13") (pinfunction "O6_13") (pintype "unspecified"))
    )
    (net (code "108") (name "Net-(U1-O7)") (class "Default")
      (node (ref "LED7") (pin "2") (pinfunction "2_2") (pintype "unspecified"))
      (node (ref "U1") (pin "12") (pinfunction "O7_12") (pintype "unspecified"))
    )
    (net (code "109") (name "Net-(U1-O8)") (class "Default")
      (node (ref "LED8") (pin "2") (pinfunction "2_2") (pintype "unspecified"))
      (node (ref "U1") (pin "11") (pinfunction "O8_11") (pintype "unspecified"))
    )
    (net (code "110") (name "Net-(U2-O1)") (class "Default")
      (node (ref "LED9") (pin "2") (pinfunction "2_2") (pintype "unspecified"))
      (node (ref "U2") (pin "18") (pinfunction "O1_18") (pintype "unspecified"))
    )
    (net (code "111") (name "Net-(U2-O2)") (class "Default")
      (node (ref "LED10") (pin "2") (pinfunction "2_2") (pintype "unspecified"))
      (node (ref "U2") (pin "17") (pinfunction "O2_17") (pintype "unspecified"))
    )
    (net (code "112") (name "Net-(U2-O3)") (class "Default")
      (node (ref "LED11") (pin "2") (pinfunction "2_2") (pintype "unspecified"))
      (node (ref "U2") (pin "16") (pinfunction "O3_16") (pintype "unspecified"))
    )
    (net (code "113") (name "Net-(U2-O4)") (class "Default")
      (node (ref "LED12") (pin "2") (pinfunction "2_2") (pintype "unspecified"))
      (node (ref "U2") (pin "15") (pinfunction "O4_15") (pintype "unspecified"))
    )
    (net (code "114") (name "Net-(U2-O5)") (class "Default")
      (node (ref "LED13") (pin "2") (pinfunction "2_2") (pintype "unspecified"))
      (node (ref "U2") (pin "14") (pinfunction "O5_14") (pintype "unspecified"))
    )
    (net (code "115") (name "Net-(U2-O6)") (class "Default")
      (node (ref "LED14") (pin "2") (pinfunction "2_2") (pintype "unspecified"))
      (node (ref "U2") (pin "13") (pinfunction "O6_13") (pintype "unspecified"))
    )
    (net (code "116") (name "Net-(U2-O7)") (class "Default")
      (node (ref "LED15") (pin "2") (pinfunction "2_2") (pintype "unspecified"))
      (node (ref "U2") (pin "12") (pinfunction "O7_12") (pintype "unspecified"))
    )
    (net (code "117") (name "Net-(U2-O8)") (class "Default")
      (node (ref "LED16") (pin "2") (pinfunction "2_2") (pintype "unspecified"))
      (node (ref "U2") (pin "11") (pinfunction "O8_11") (pintype "unspecified"))
    )
    (net (code "118") (name "Net-(U3-O1)") (class "Default")
      (node (ref "LED17") (pin "2") (pinfunction "2_2") (pintype "unspecified"))
      (node (ref "U3") (pin "18") (pinfunction "O1_18") (pintype "unspecified"))
    )
    (net (code "119") (name "Net-(U3-O2)") (class "Default")
      (node (ref "LED18") (pin "2") (pinfunction "2_2") (pintype "unspecified"))
      (node (ref "U3") (pin "17") (pinfunction "O2_17") (pintype "unspecified"))
    )
    (net (code "120") (name "Net-(U3-O3)") (class "Default")
      (node (ref "LED19") (pin "2") (pinfunction "2_2") (pintype "unspecified"))
      (node (ref "U3") (pin "16") (pinfunction "O3_16") (pintype "unspecified"))
    )
    (net (code "121") (name "Net-(U3-O4)") (class "Default")
      (node (ref "LED20") (pin "2") (pinfunction "2_2") (pintype "unspecified"))
      (node (ref "U3") (pin "15") (pinfunction "O4_15") (pintype "unspecified"))
    )
    (net (code "122") (name "Net-(U3-O5)") (class "Default")
      (node (ref "LED21") (pin "2") (pinfunction "2_2") (pintype "unspecified"))
      (node (ref "U3") (pin "14") (pinfunction "O5_14") (pintype "unspecified"))
    )
    (net (code "123") (name "Net-(U3-O6)") (class "Default")
      (node (ref "LED22") (pin "2") (pinfunction "2_2") (pintype "unspecified"))
      (node (ref "U3") (pin "13") (pinfunction "O6_13") (pintype "unspecified"))
    )
    (net (code "124") (name "Net-(U3-O7)") (class "Default")
      (node (ref "LED23") (pin "2") (pinfunction "2_2") (pintype "unspecified"))
      (node (ref "U3") (pin "12") (pinfunction "O7_12") (pintype "unspecified"))
    )
    (net (code "125") (name "Net-(U3-O8)") (class "Default")
      (node (ref "LED24") (pin "2") (pinfunction "2_2") (pintype "unspecified"))
      (node (ref "U3") (pin "11") (pinfunction "O8_11") (pintype "unspecified"))
    )
    (net (code "126") (name "Net-(U4-O1)") (class "Default")
      (node (ref "LED25") (pin "2") (pinfunction "2_2") (pintype "unspecified"))
      (node (ref "U4") (pin "18") (pinfunction "O1_18") (pintype "unspecified"))
    )
    (net (code "127") (name "Net-(U4-O2)") (class "Default")
      (node (ref "LED26") (pin "2") (pinfunction "2_2") (pintype "unspecified"))
      (node (ref "U4") (pin "17") (pinfunction "O2_17") (pintype "unspecified"))
    )
    (net (code "128") (name "Net-(U4-O3)") (class "Default")
      (node (ref "LED27") (pin "2") (pinfunction "2_2") (pintype "unspecified"))
      (node (ref "U4") (pin "16") (pinfunction "O3_16") (pintype "unspecified"))
    )
    (net (code "129") (name "Net-(U4-O4)") (class "Default")
      (node (ref "LED28") (pin "2") (pinfunction "2_2") (pintype "unspecified"))
      (node (ref "U4") (pin "15") (pinfunction "O4_15") (pintype "unspecified"))
    )
    (net (code "130") (name "Net-(U4-O5)") (class "Default")
      (node (ref "LED29") (pin "2") (pinfunction "2_2") (pintype "unspecified"))
      (node (ref "U4") (pin "14") (pinfunction "O5_14") (pintype "unspecified"))
    )
    (net (code "131") (name "Net-(U4-O6)") (class "Default")
      (node (ref "LED30") (pin "2") (pinfunction "2_2") (pintype "unspecified"))
      (node (ref "U4") (pin "13") (pinfunction "O6_13") (pintype "unspecified"))
    )
    (net (code "132") (name "Net-(U4-O7)") (class "Default")
      (node (ref "LED31") (pin "2") (pinfunction "2_2") (pintype "unspecified"))
      (node (ref "U4") (pin "12") (pinfunction "O7_12") (pintype "unspecified"))
    )
    (net (code "133") (name "Net-(U4-O8)") (class "Default")
      (node (ref "LED32") (pin "2") (pinfunction "2_2") (pintype "unspecified"))
      (node (ref "U4") (pin "11") (pinfunction "O8_11") (pintype "unspecified"))
    )
    (net (code "134") (name "Net-(U5-O1)") (class "Default")
      (node (ref "LED33") (pin "2") (pinfunction "2_2") (pintype "unspecified"))
      (node (ref "U5") (pin "18") (pinfunction "O1_18") (pintype "unspecified"))
    )
    (net (code "135") (name "Net-(U5-O2)") (class "Default")
      (node (ref "LED34") (pin "2") (pinfunction "2_2") (pintype "unspecified"))
      (node (ref "U5") (pin "17") (pinfunction "O2_17") (pintype "unspecified"))
    )
    (net (code "136") (name "Net-(U5-O3)") (class "Default")
      (node (ref "LED35") (pin "2") (pinfunction "2_2") (pintype "unspecified"))
      (node (ref "U5") (pin "16") (pinfunction "O3_16") (pintype "unspecified"))
    )
    (net (code "137") (name "Net-(U5-O4)") (class "Default")
      (node (ref "LED36") (pin "2") (pinfunction "2_2") (pintype "unspecified"))
      (node (ref "U5") (pin "15") (pinfunction "O4_15") (pintype "unspecified"))
    )
    (net (code "138") (name "Net-(U5-O5)") (class "Default")
      (node (ref "LED37") (pin "2") (pinfunction "2_2") (pintype "unspecified"))
      (node (ref "U5") (pin "14") (pinfunction "O5_14") (pintype "unspecified"))
    )
    (net (code "139") (name "Net-(U5-O6)") (class "Default")
      (node (ref "LED38") (pin "2") (pinfunction "2_2") (pintype "unspecified"))
      (node (ref "U5") (pin "13") (pinfunction "O6_13") (pintype "unspecified"))
    )
    (net (code "140") (name "Net-(U5-O7)") (class "Default")
      (node (ref "LED39") (pin "2") (pinfunction "2_2") (pintype "unspecified"))
      (node (ref "U5") (pin "12") (pinfunction "O7_12") (pintype "unspecified"))
    )
    (net (code "141") (name "Net-(U5-O8)") (class "Default")
      (node (ref "LED40") (pin "2") (pinfunction "2_2") (pintype "unspecified"))
      (node (ref "U5") (pin "11") (pinfunction "O8_11") (pintype "unspecified"))
    )
    (net (code "142") (name "Net-(U6-O1)") (class "Default")
      (node (ref "LED41") (pin "2") (pinfunction "2_2") (pintype "unspecified"))
      (node (ref "U6") (pin "18") (pinfunction "O1_18") (pintype "unspecified"))
    )
    (net (code "143") (name "Net-(U6-O2)") (class "Default")
      (node (ref "LED42") (pin "2") (pinfunction "2_2") (pintype "unspecified"))
      (node (ref "U6") (pin "17") (pinfunction "O2_17") (pintype "unspecified"))
    )
    (net (code "144") (name "Net-(U6-O3)") (class "Default")
      (node (ref "LED43") (pin "2") (pinfunction "2_2") (pintype "unspecified"))
      (node (ref "U6") (pin "16") (pinfunction "O3_16") (pintype "unspecified"))
    )
    (net (code "145") (name "Net-(U6-O4)") (class "Default")
      (node (ref "LED44") (pin "2") (pinfunction "2_2") (pintype "unspecified"))
      (node (ref "U6") (pin "15") (pinfunction "O4_15") (pintype "unspecified"))
    )
    (net (code "146") (name "Net-(U6-O5)") (class "Default")
      (node (ref "LED45") (pin "2") (pinfunction "2_2") (pintype "unspecified"))
      (node (ref "U6") (pin "14") (pinfunction "O5_14") (pintype "unspecified"))
    )
    (net (code "147") (name "Net-(U6-O6)") (class "Default")
      (node (ref "LED46") (pin "2") (pinfunction "2_2") (pintype "unspecified"))
      (node (ref "U6") (pin "13") (pinfunction "O6_13") (pintype "unspecified"))
    )
    (net (code "148") (name "Net-(U6-O7)") (class "Default")
      (node (ref "LED47") (pin "2") (pinfunction "2_2") (pintype "unspecified"))
      (node (ref "U6") (pin "12") (pinfunction "O7_12") (pintype "unspecified"))
    )
    (net (code "149") (name "Net-(U6-O8)") (class "Default")
      (node (ref "LED48") (pin "2") (pinfunction "2_2") (pintype "unspecified"))
      (node (ref "U6") (pin "11") (pinfunction "O8_11") (pintype "unspecified"))
    )
    (net (code "150") (name "unconnected-(CN_1-Pad4)") (class "Default")
      (node (ref "CN_1") (pin "4") (pinfunction "4_4") (pintype "input+no_connect"))
    )
    (net (code "151") (name "unconnected-(CN_1-Pad8)") (class "Default")
      (node (ref "CN_1") (pin "8") (pinfunction "8_8") (pintype "input+no_connect"))
    )
    (net (code "152") (name "unconnected-(CN_1-Pad9)") (class "Default")
      (node (ref "CN_1") (pin "9") (pinfunction "9_9") (pintype "input+no_connect"))
    )
    (net (code "153") (name "unconnected-(CN_1-Pad10)") (class "Default")
      (node (ref "CN_1") (pin "10") (pinfunction "10_10") (pintype "input+no_connect"))
    )
    (net (code "154") (name "unconnected-(CN_1-Pad11)") (class "Default")
      (node (ref "CN_1") (pin "11") (pinfunction "11_11") (pintype "input+no_connect"))
    )
    (net (code "155") (name "unconnected-(CN_1-Pad12)") (class "Default")
      (node (ref "CN_1") (pin "12") (pinfunction "12_12") (pintype "input+no_connect"))
    )
    (net (code "156") (name "unconnected-(CN_1-Pad13)") (class "Default")
      (node (ref "CN_1") (pin "13") (pinfunction "13_13") (pintype "input+no_connect"))
    )
    (net (code "157") (name "unconnected-(CN_1-Pad14)") (class "Default")
      (node (ref "CN_1") (pin "14") (pinfunction "14_14") (pintype "input+no_connect"))
    )
    (net (code "158") (name "unconnected-(CN_1-Pad15)") (class "Default")
      (node (ref "CN_1") (pin "15") (pinfunction "15_15") (pintype "input+no_connect"))
    )
    (net (code "159") (name "unconnected-(CN_1-Pad16)") (class "Default")
      (node (ref "CN_1") (pin "16") (pinfunction "16_16") (pintype "input+no_connect"))
    )
    (net (code "160") (name "unconnected-(CN_2-Pad3)") (class "Default")
      (node (ref "CN_2") (pin "3") (pinfunction "3_3") (pintype "input+no_connect"))
    )
    (net (code "161") (name "unconnected-(CN_2-Pad4)") (class "Default")
      (node (ref "CN_2") (pin "4") (pinfunction "4_4") (pintype "input+no_connect"))
    )
    (net (code "162") (name "unconnected-(CN_2-Pad5)") (class "Default")
      (node (ref "CN_2") (pin "5") (pinfunction "5_5") (pintype "input+no_connect"))
    )
    (net (code "163") (name "unconnected-(CN_2-Pad6)") (class "Default")
      (node (ref "CN_2") (pin "6") (pinfunction "6_6") (pintype "input+no_connect"))
    )
    (net (code "164") (name "unconnected-(CN_2-Pad7)") (class "Default")
      (node (ref "CN_2") (pin "7") (pinfunction "7_7") (pintype "input+no_connect"))
    )
    (net (code "165") (name "unconnected-(CN_2-Pad8)") (class "Default")
      (node (ref "CN_2") (pin "8") (pinfunction "8_8") (pintype "input+no_connect"))
    )
    (net (code "166") (name "unconnected-(CN_2-Pad9)") (class "Default")
      (node (ref "CN_2") (pin "9") (pinfunction "9_9") (pintype "input+no_connect"))
    )
    (net (code "167") (name "unconnected-(CN_2-Pad10)") (class "Default")
      (node (ref "CN_2") (pin "10") (pinfunction "10_10") (pintype "input+no_connect"))
    )
    (net (code "168") (name "unconnected-(CN_2-Pad11)") (class "Default")
      (node (ref "CN_2") (pin "11") (pinfunction "11_11") (pintype "input+no_connect"))
    )
    (net (code "169") (name "unconnected-(CN_2-Pad12)") (class "Default")
      (node (ref "CN_2") (pin "12") (pinfunction "12_12") (pintype "input+no_connect"))
    )
    (net (code "170") (name "unconnected-(RN1-Pad2)") (class "Default")
      (node (ref "RN1") (pin "2") (pinfunction "2_2") (pintype "unspecified+no_connect"))
    )
    (net (code "171") (name "unconnected-(RN2-Pad2)") (class "Default")
      (node (ref "RN2") (pin "2") (pinfunction "2_2") (pintype "unspecified+no_connect"))
    )
    (net (code "172") (name "unconnected-(RN3-Pad2)") (class "Default")
      (node (ref "RN3") (pin "2") (pinfunction "2_2") (pintype "unspecified+no_connect"))
    )
    (net (code "173") (name "unconnected-(RN4-Pad2)") (class "Default")
      (node (ref "RN4") (pin "2") (pinfunction "2_2") (pintype "unspecified+no_connect"))
    )
    (net (code "174") (name "unconnected-(RN5-Pad2)") (class "Default")
      (node (ref "RN5") (pin "2") (pinfunction "2_2") (pintype "unspecified+no_connect"))
    )
    (net (code "175") (name "unconnected-(RN6-Pad2)") (class "Default")
      (node (ref "RN6") (pin "2") (pinfunction "2_2") (pintype "unspecified+no_connect"))
    )
  )
)
